# Power_Regulation.net
KiCad netlist of a schematic drawn in Altium Designer
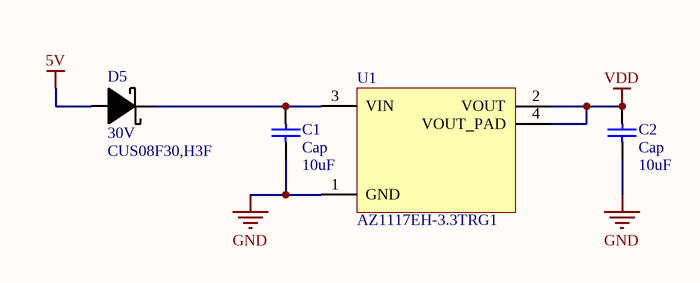
[diagram p0: Power_Regulation.SchDoc]

(export (version "E")
  (design (tool "Eeschema 10.0.6"))
  (components
    (comp (ref "C1")
      (value "Cap")
      (footprint "C0805")
      (description "Capacitor")
      (fields (field (name "ALTIUM_VALUE") "10uF") (field (name "PUBLISHER") "Altium Limited"))
      (libsource (lib "Capacitors") (part "Cap"))
    )
    (comp (ref "C2")
      (value "Cap")
      (footprint "C0805")
      (description "Capacitor")
      (fields (field (name "ALTIUM_VALUE") "10uF") (field (name "PUBLISHER") "Altium Limited"))
      (libsource (lib "Capacitors") (part "Cap"))
    )
    (comp (ref "D5")
      (value "Schottky Diode")
      (footprint "SOD323")
      (description "Diode Schottky 30V 800mA (DC) Surface Mount SOD-323")
      (fields
        (field (name "MANUFACTURER") "Toshiba Semiconductor and Storage")
        (field (name "VOLTAGE - DC REVERSE (VR) (MAX)") "30V")
        (field (name "MANUFACTURER PART NUMBER") "CUS08F30,H3F")
      )
      (libsource (lib "FC") (part "DS_CUS08F30"))
    )
    (comp (ref "U1")
      (value "U_AZ1117EH-3.3TRG1")
      (footprint "SOT223")
      (description "IC LDO 3.3V 1A")
      (fields
        (field (name "MANUFACTURER") "Diodes Incorporated")
        (field (name "MANUFACTURER PART NUMBER") "AZ1117EH-3.3TRG1")
      )
      (libsource (lib "FC") (part "U_AZ1117EH-3.3TRG1"))
    )
  )
  (nets
    (net (code "1") (name "5V") (class "Default")
      (node (ref "D5") (pin "2") (pinfunction "AN_2") (pintype "passive"))
    )
    (net (code "2") (name "GND") (class "Default")
      (node (ref "C1") (pin "1") (pinfunction "1_1") (pintype "passive"))
      (node (ref "C2") (pin "1") (pinfunction "1_1") (pintype "passive"))
      (node (ref "U1") (pin "1") (pinfunction "GND_1") (pintype "power_in"))
    )
    (net (code "3") (name "Net-(D5-CA)") (class "Default")
      (node (ref "C1") (pin "2") (pinfunction "2_2") (pintype "passive"))
      (node (ref "D5") (pin "1") (pinfunction "CA_1") (pintype "passive"))
      (node (ref "U1") (pin "3") (pinfunction "VIN_3") (pintype "power_in"))
    )
    (net (code "4") (name "VDD") (class "Default")
      (node (ref "C2") (pin "2") (pinfunction "2_2") (pintype "passive"))
      (node (ref "U1") (pin "2") (pinfunction "VOUT_2") (pintype "power_in"))
      (node (ref "U1") (pin "4") (pinfunction "VOUT_PAD_4") (pintype "power_in"))
    )
  )
)
